# PS.net
KiCad netlist of a schematic drawn in EAGLE
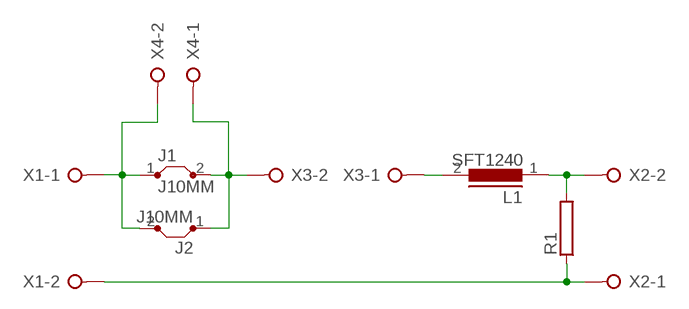
[diagram p0: schematic, sheet 1]

(export (version "E")
  (design (tool "Eeschema 10.0.6"))
  (components
    (comp (ref "J1")
      (value "J10MM")
      (footprint "eagle-import:10")
      (libsource (lib "eagle-import") (part "J10MM"))
    )
    (comp (ref "J2")
      (value "J10MM")
      (footprint "eagle-import:10")
      (libsource (lib "eagle-import") (part "J10MM"))
    )
    (comp (ref "L1")
      (value "SFT1240")
      (footprint "eagle-import:SFT1240")
      (libsource (lib "eagle-import") (part "SFT1240"))
    )
    (comp (ref "R1")
      (value "RAC04")
      (footprint "eagle-import:AC04")
      (libsource (lib "eagle-import") (part "RAC04"))
    )
    (comp (ref "X1")
      (value "W237-02P")
      (footprint "eagle-import:W237-132")
      (libsource (lib "eagle-import") (part "W237-02P"))
    )
    (comp (ref "X2")
      (value "W237-02P")
      (footprint "eagle-import:W237-132")
      (libsource (lib "eagle-import") (part "W237-02P"))
    )
    (comp (ref "X3")
      (value "W237-02P")
      (footprint "eagle-import:W237-132")
      (libsource (lib "eagle-import") (part "W237-02P"))
    )
    (comp (ref "X4")
      (value "W237-02P")
      (footprint "eagle-import:W237-132")
      (libsource (lib "eagle-import") (part "W237-02P"))
    )
  )
  (nets
    (net (code "1") (name "Net-(X1A-KL)") (class "Default")
      (node (ref "J1") (pin "1") (pinfunction "1_1") (pintype "passive"))
      (node (ref "J2") (pin "2") (pinfunction "2_2") (pintype "passive"))
      (node (ref "X1") (pin "1") (pinfunction "KL_1") (pintype "passive"))
      (node (ref "X4") (pin "2") (pinfunction "KL_2") (pintype "passive"))
    )
    (net (code "2") (name "Net-(X1B-KL)") (class "Default")
      (node (ref "R1") (pin "1") (pinfunction "1_1") (pintype "passive"))
      (node (ref "X1") (pin "2") (pinfunction "KL_2") (pintype "passive"))
      (node (ref "X2") (pin "1") (pinfunction "KL_1") (pintype "passive"))
    )
    (net (code "3") (name "Net-(X2B-KL)") (class "Default")
      (node (ref "L1") (pin "1") (pinfunction "1_1") (pintype "passive"))
      (node (ref "R1") (pin "2") (pinfunction "2_2") (pintype "passive"))
      (node (ref "X2") (pin "2") (pinfunction "KL_2") (pintype "passive"))
    )
    (net (code "4") (name "Net-(X3A-KL)") (class "Default")
      (node (ref "L1") (pin "2") (pinfunction "2_2") (pintype "passive"))
      (node (ref "X3") (pin "1") (pinfunction "KL_1") (pintype "passive"))
    )
    (net (code "5") (name "Net-(X3B-KL)") (class "Default")
      (node (ref "J1") (pin "2") (pinfunction "2_2") (pintype "passive"))
      (node (ref "J2") (pin "1") (pinfunction "1_1") (pintype "passive"))
      (node (ref "X3") (pin "2") (pinfunction "KL_2") (pintype "passive"))
      (node (ref "X4") (pin "1") (pinfunction "KL_1") (pintype "passive"))
    )
  )
)
